# NEW-PCB.net
KiCad netlist of a schematic drawn in EAGLE
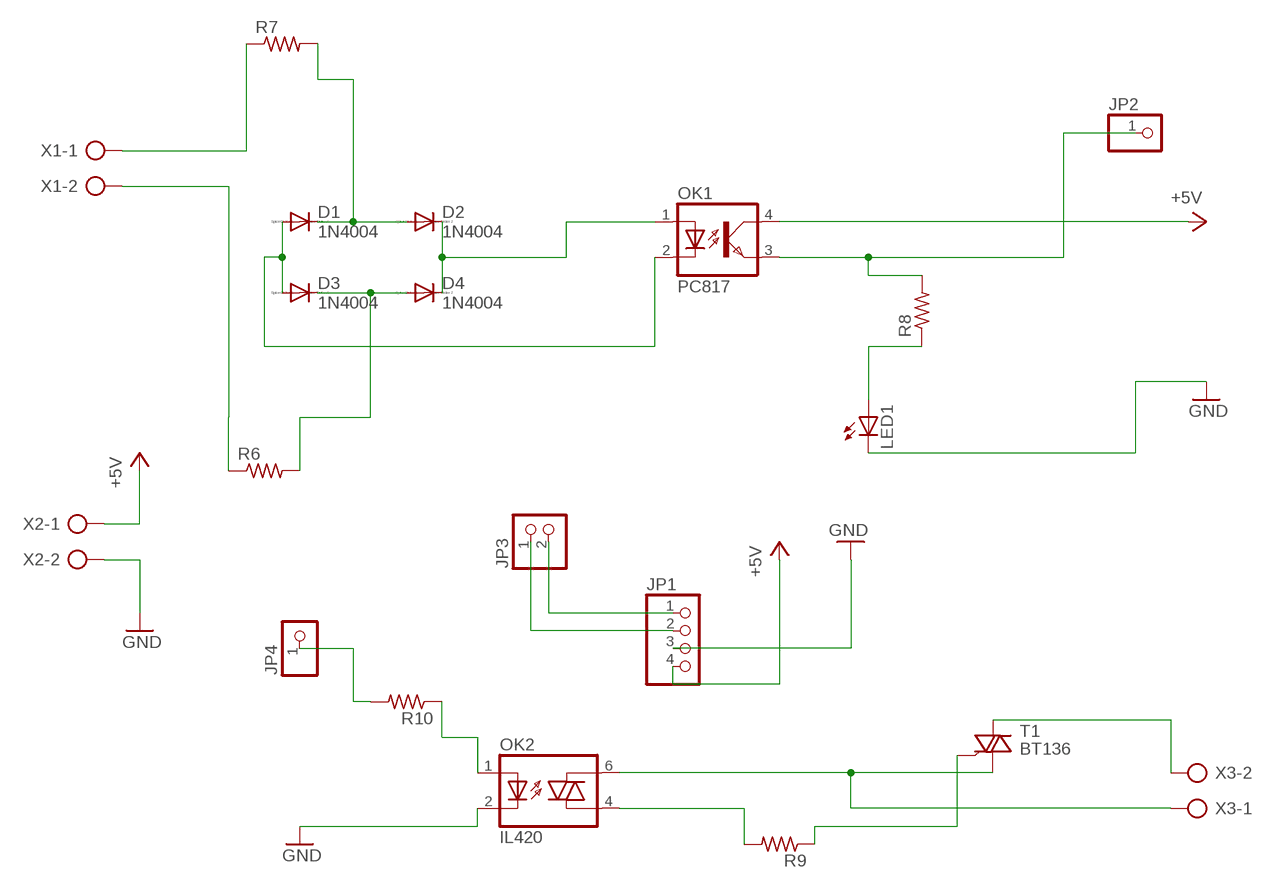
[diagram p0: schematic, sheet 1]

(export (version "E")
  (design (tool "Eeschema 10.0.6"))
  (components
    (comp (ref "D1")
      (value "1N4004")
      (footprint "eagle-import:DO41-10")
      (libsource (lib "eagle-import") (part "1N4004"))
    )
    (comp (ref "D2")
      (value "1N4004")
      (footprint "eagle-import:DO41-10")
      (libsource (lib "eagle-import") (part "1N4004"))
    )
    (comp (ref "D3")
      (value "1N4004")
      (footprint "eagle-import:DO41-10")
      (libsource (lib "eagle-import") (part "1N4004"))
    )
    (comp (ref "D4")
      (value "1N4004")
      (footprint "eagle-import:DO41-10")
      (libsource (lib "eagle-import") (part "1N4004"))
    )
    (comp (ref "JP1")
      (value "PINHD-1X4")
      (footprint "eagle-import:1X04")
      (libsource (lib "eagle-import") (part "PINHD-1X4"))
    )
    (comp (ref "JP2")
      (value "PINHD-1X1")
      (footprint "eagle-import:1X01")
      (libsource (lib "eagle-import") (part "PINHD-1X1"))
    )
    (comp (ref "JP3")
      (value "PINHD-1X2")
      (footprint "eagle-import:1X02")
      (libsource (lib "eagle-import") (part "PINHD-1X2"))
    )
    (comp (ref "JP4")
      (value "PINHD-1X1")
      (footprint "eagle-import:1X01")
      (libsource (lib "eagle-import") (part "PINHD-1X1"))
    )
    (comp (ref "LED1")
      (value "LED5MM")
      (footprint "eagle-import:LED5MM")
      (libsource (lib "eagle-import") (part "LED5MM"))
    )
    (comp (ref "OK1")
      (value "PC817")
      (footprint "eagle-import:DIL04")
      (fields (field (name "MPN") "PC817X4J000F"))
      (libsource (lib "eagle-import") (part "PC817"))
    )
    (comp (ref "OK2")
      (value "IL420")
      (footprint "eagle-import:DIL06")
      (fields (field (name "MF") "VISHAY/TELEFUNKEN"))
      (libsource (lib "eagle-import") (part "IL420"))
    )
    (comp (ref "R6")
      (value "R-US_0411/15")
      (footprint "eagle-import:0411_15")
      (libsource (lib "eagle-import") (part "R-US_0411/15"))
    )
    (comp (ref "R7")
      (value "R-US_0411/15")
      (footprint "eagle-import:0411_15")
      (libsource (lib "eagle-import") (part "R-US_0411/15"))
    )
    (comp (ref "R8")
      (value "R-US_0411/15")
      (footprint "eagle-import:0411_15")
      (libsource (lib "eagle-import") (part "R-US_0411/15"))
    )
    (comp (ref "R9")
      (value "R-US_0411/15")
      (footprint "eagle-import:0411_15")
      (libsource (lib "eagle-import") (part "R-US_0411/15"))
    )
    (comp (ref "R10")
      (value "R-US_0411/15")
      (footprint "eagle-import:0411_15")
      (libsource (lib "eagle-import") (part "R-US_0411/15"))
    )
    (comp (ref "T1")
      (value "BT136")
      (footprint "eagle-import:TO220AB")
      (libsource (lib "eagle-import") (part "BT136"))
    )
    (comp (ref "X1")
      (value "AK300/2")
      (footprint "eagle-import:AK300_2")
      (libsource (lib "eagle-import") (part "AK300/2"))
    )
    (comp (ref "X2")
      (value "AK300/2")
      (footprint "eagle-import:AK300_2")
      (libsource (lib "eagle-import") (part "AK300/2"))
    )
    (comp (ref "X3")
      (value "AK300/2")
      (footprint "eagle-import:AK300_2")
      (libsource (lib "eagle-import") (part "AK300/2"))
    )
  )
  (nets
    (net (code "1") (name "+5V") (class "Default")
      (node (ref "JP1") (pin "4") (pinfunction "4_4") (pintype "passive"))
      (node (ref "OK1") (pin "4") (pinfunction "COL_4") (pintype "passive"))
      (node (ref "X2") (pin "1") (pinfunction "KL_1") (pintype "passive"))
    )
    (net (code "2") (name "GND") (class "Default")
      (node (ref "JP1") (pin "3") (pinfunction "3_3") (pintype "passive"))
      (node (ref "LED1") (pin "K") (pinfunction "C_K") (pintype "passive"))
      (node (ref "OK2") (pin "2") (pinfunction "C_2") (pintype "passive"))
      (node (ref "X2") (pin "2") (pinfunction "KL_2") (pintype "passive"))
    )
    (net (code "3") (name "Net-(D1-PadC)") (class "Default")
      (node (ref "D1") (pin "C") (pinfunction "C_C") (pintype "passive"))
      (node (ref "D2") (pin "A") (pinfunction "A_A") (pintype "passive"))
      (node (ref "R7") (pin "2") (pinfunction "2_2") (pintype "passive"))
    )
    (net (code "4") (name "Net-(D3-PadC)") (class "Default")
      (node (ref "D3") (pin "C") (pinfunction "C_C") (pintype "passive"))
      (node (ref "D4") (pin "A") (pinfunction "A_A") (pintype "passive"))
      (node (ref "R6") (pin "2") (pinfunction "2_2") (pintype "passive"))
    )
    (net (code "5") (name "Net-(JP1-Pad1)") (class "Default")
      (node (ref "JP1") (pin "1") (pinfunction "1_1") (pintype "passive"))
      (node (ref "JP3") (pin "2") (pinfunction "2_2") (pintype "passive"))
    )
    (net (code "6") (name "Net-(JP1-Pad2)") (class "Default")
      (node (ref "JP1") (pin "2") (pinfunction "2_2") (pintype "passive"))
      (node (ref "JP3") (pin "1") (pinfunction "1_1") (pintype "passive"))
    )
    (net (code "7") (name "Net-(JP4-Pad1)") (class "Default")
      (node (ref "JP4") (pin "1") (pinfunction "1_1") (pintype "passive"))
      (node (ref "R10") (pin "2") (pinfunction "2_2") (pintype "passive"))
    )
    (net (code "8") (name "Net-(LED1-PadA)") (class "Default")
      (node (ref "LED1") (pin "A") (pinfunction "A_A") (pintype "passive"))
      (node (ref "R8") (pin "1") (pinfunction "1_1") (pintype "passive"))
    )
    (net (code "9") (name "Net-(OK1-A)") (class "Default")
      (node (ref "D2") (pin "C") (pinfunction "C_C") (pintype "passive"))
      (node (ref "D4") (pin "C") (pinfunction "C_C") (pintype "passive"))
      (node (ref "OK1") (pin "1") (pinfunction "A_1") (pintype "passive"))
    )
    (net (code "10") (name "Net-(OK1-C)") (class "Default")
      (node (ref "D1") (pin "A") (pinfunction "A_A") (pintype "passive"))
      (node (ref "D3") (pin "A") (pinfunction "A_A") (pintype "passive"))
      (node (ref "OK1") (pin "2") (pinfunction "C_2") (pintype "passive"))
    )
    (net (code "11") (name "Net-(OK1-EMIT)") (class "Default")
      (node (ref "JP2") (pin "1") (pinfunction "1_1") (pintype "passive"))
      (node (ref "OK1") (pin "3") (pinfunction "EMIT_3") (pintype "passive"))
      (node (ref "R8") (pin "2") (pinfunction "2_2") (pintype "passive"))
    )
    (net (code "12") (name "Net-(OK2-A)") (class "Default")
      (node (ref "OK2") (pin "1") (pinfunction "A_1") (pintype "passive"))
      (node (ref "R10") (pin "1") (pinfunction "1_1") (pintype "passive"))
    )
    (net (code "13") (name "Net-(OK2-A1)") (class "Default")
      (node (ref "OK2") (pin "4") (pinfunction "A1_4") (pintype "passive"))
      (node (ref "R9") (pin "2") (pinfunction "2_2") (pintype "passive"))
    )
    (net (code "14") (name "Net-(OK2-A2)") (class "Default")
      (node (ref "OK2") (pin "6") (pinfunction "A2_6") (pintype "passive"))
      (node (ref "T1") (pin "1") (pinfunction "A1_1") (pintype "passive"))
      (node (ref "X3") (pin "1") (pinfunction "KL_1") (pintype "passive"))
    )
    (net (code "15") (name "Net-(T1-A2)") (class "Default")
      (node (ref "T1") (pin "2") (pinfunction "A2_2") (pintype "passive"))
      (node (ref "X3") (pin "2") (pinfunction "KL_2") (pintype "passive"))
    )
    (net (code "16") (name "Net-(T1-G)") (class "Default")
      (node (ref "R9") (pin "1") (pinfunction "1_1") (pintype "passive"))
      (node (ref "T1") (pin "3") (pinfunction "G_3") (pintype "passive"))
    )
    (net (code "17") (name "Net-(X1A-KL)") (class "Default")
      (node (ref "R7") (pin "1") (pinfunction "1_1") (pintype "passive"))
      (node (ref "X1") (pin "1") (pinfunction "KL_1") (pintype "passive"))
    )
    (net (code "18") (name "Net-(X1B-KL)") (class "Default")
      (node (ref "R6") (pin "1") (pinfunction "1_1") (pintype "passive"))
      (node (ref "X1") (pin "2") (pinfunction "KL_2") (pintype "passive"))
    )
  )
)
